# SCH_Fulcrum-Analog-FCU_2024-12-11.net
KiCad netlist of a schematic drawn in EasyEDA
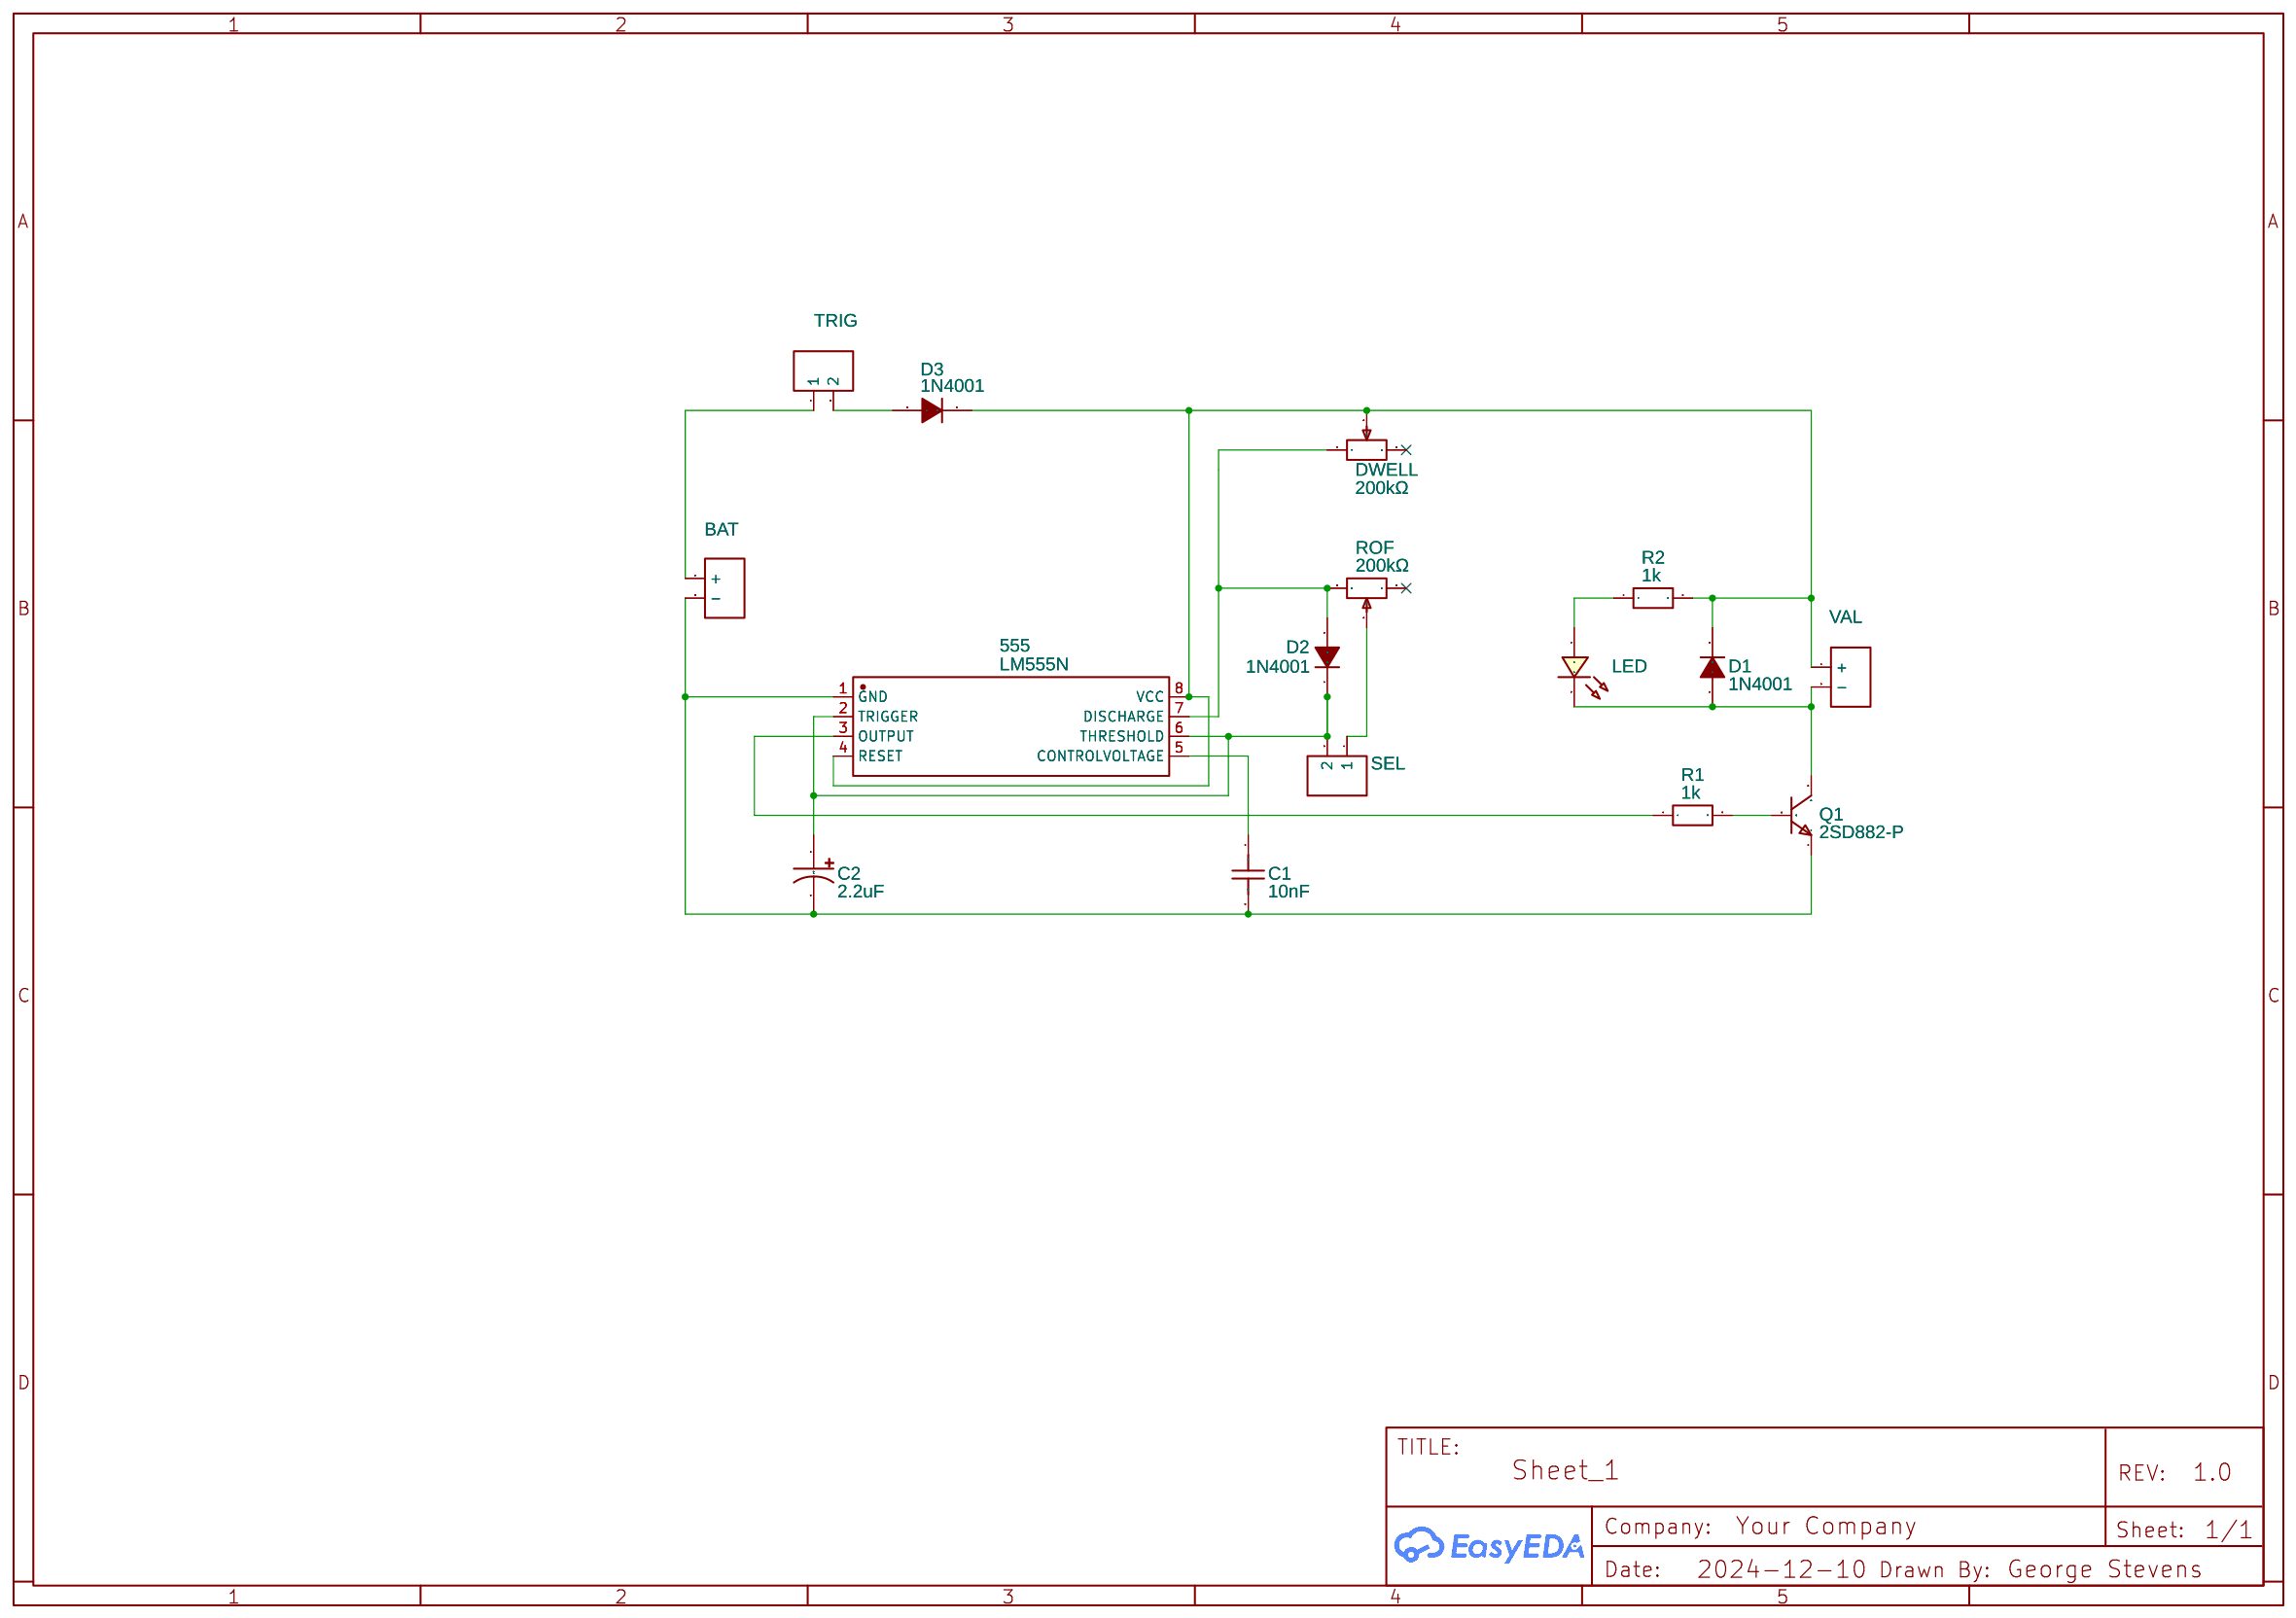
[diagram p0: schematic sheet]

(export (version "E")
  (design (tool "Eeschema 10.0.6"))
  (components
    (comp (ref "555")
      (value "LM555N")
      (fields (field (name "Manufacturer") "HGSEMI(华冠)"))
      (libsource (lib "") (part "LM555N"))
    )
    (comp (ref "BAT") (value "HDR-M-2.54_1x2") (libsource (lib "") (part "HDR-M-2.54_1x2")))
    (comp (ref "C1")
      (value "10nF")
      (fields (field (name "Manufacturer Part") "CL112J103J0501") (field (name "Manufacturer") "KYET(科雅)"))
      (libsource (lib "") (part "CL112J103J0501"))
    )
    (comp (ref "C2")
      (value "2.2uF")
      (fields
        (field (name "Manufacturer Part") "ECG1HM2R2D11OTBO")
        (field (name "Manufacturer") "Yunxing(云星)")
      )
      (libsource (lib "") (part "ECG1HM2R2D11OTBO"))
    )
    (comp (ref "D1")
      (value "1N4001")
      (fields (field (name "Manufacturer") "MDD(辰达半导体)"))
      (libsource (lib "") (part "1N4001_C2456"))
    )
    (comp (ref "D2")
      (value "1N4001")
      (fields (field (name "Manufacturer") "MDD(辰达半导体)"))
      (libsource (lib "") (part "1N4001_C2456_1"))
    )
    (comp (ref "D3")
      (value "1N4001")
      (fields (field (name "Manufacturer") "MDD(辰达半导体)"))
      (libsource (lib "") (part "1N4001_C2456_2"))
    )
    (comp (ref "DWELL")
      (value "200kΩ")
      (fields (field (name "Manufacturer Part") "RM063-204(200K)") (field (name "Manufacturer") "BOCHEN(博晨)"))
      (libsource (lib "") (part "RM063-204(200K)_1"))
    )
    (comp (ref "LED")
      (value "LED-TH-3mm_R")
      (fields
        (field (name "Manufacturer Part") "204-10SDRD/S530-A3-L")
        (field (name "Manufacturer") "EVERLIGHT(台湾亿光)")
      )
      (libsource (lib "") (part "LED-TH-3mm_R"))
    )
    (comp (ref "Q1")
      (value "2SD882-P")
      (fields (field (name "Manufacturer") "BLUE ROCKET(蓝箭)"))
      (libsource (lib "") (part "2SD882-P"))
    )
    (comp (ref "R1") (value "1k") (libsource (lib "") (part "R_AXIAL-0.4_EU")))
    (comp (ref "R2") (value "1k") (libsource (lib "") (part "R_AXIAL-0.4_EU")))
    (comp (ref "ROF")
      (value "200kΩ")
      (fields (field (name "Manufacturer Part") "RM063-204(200K)") (field (name "Manufacturer") "BOCHEN(博晨)"))
      (libsource (lib "") (part "RM063-204(200K)"))
    )
    (comp (ref "SEL") (value "HDR-M-2.54_1x2") (libsource (lib "") (part "HDR-M-2.54_1x2_3")))
    (comp (ref "TRIG") (value "HDR-M-2.54_1x2") (libsource (lib "") (part "HDR-M-2.54_1x2_2")))
    (comp (ref "VAL") (value "HDR-M-2.54_1x2") (libsource (lib "") (part "HDR-M-2.54_1x2_1")))
  )
  (nets
    (net (code "1") (name "Net-(555-CONTROLVOLTAGE)") (class "Default")
      (node (ref "555") (pin "5") (pinfunction "CONTROLVOLTAGE_5") (pintype "unspecified"))
      (node (ref "C1") (pin "1") (pinfunction "1_1") (pintype "unspecified"))
    )
    (net (code "2") (name "Net-(555-DISCHARGE)") (class "Default")
      (node (ref "555") (pin "7") (pinfunction "DISCHARGE_7") (pintype "unspecified"))
      (node (ref "D2") (pin "2") (pinfunction "A_2") (pintype "unspecified"))
      (node (ref "DWELL") (pin "1") (pinfunction "1_1") (pintype "input"))
      (node (ref "ROF") (pin "3") (pinfunction "3_3") (pintype "input"))
    )
    (net (code "3") (name "Net-(555-GND)") (class "Default")
      (node (ref "555") (pin "1") (pinfunction "GND_1") (pintype "unspecified"))
      (node (ref "BAT") (pin "2") (pinfunction "-_2") (pintype "unspecified"))
      (node (ref "C1") (pin "2") (pinfunction "2_2") (pintype "unspecified"))
      (node (ref "C2") (pin "2") (pinfunction "2_2") (pintype "unspecified"))
      (node (ref "Q1") (pin "1") (pinfunction "E_1") (pintype "unspecified"))
    )
    (net (code "4") (name "Net-(555-OUTPUT)") (class "Default")
      (node (ref "555") (pin "3") (pinfunction "OUTPUT_3") (pintype "unspecified"))
      (node (ref "R1") (pin "1") (pinfunction "1_1") (pintype "unspecified"))
    )
    (net (code "5") (name "Net-(555-RESET)") (class "Default")
      (node (ref "555") (pin "4") (pinfunction "RESET_4") (pintype "unspecified"))
      (node (ref "555") (pin "8") (pinfunction "VCC_8") (pintype "unspecified"))
      (node (ref "D1") (pin "1") (pinfunction "C_1") (pintype "unspecified"))
      (node (ref "D3") (pin "1") (pinfunction "C_1") (pintype "unspecified"))
      (node (ref "DWELL") (pin "2") (pinfunction "2_2") (pintype "input"))
      (node (ref "R2") (pin "2") (pinfunction "2_2") (pintype "unspecified"))
      (node (ref "VAL") (pin "1") (pinfunction "+_1") (pintype "unspecified"))
    )
    (net (code "6") (name "Net-(555-THRESHOLD)") (class "Default")
      (node (ref "555") (pin "2") (pinfunction "TRIGGER_2") (pintype "unspecified"))
      (node (ref "555") (pin "6") (pinfunction "THRESHOLD_6") (pintype "unspecified"))
      (node (ref "C2") (pin "1") (pinfunction "1_1") (pintype "unspecified"))
      (node (ref "D2") (pin "1") (pinfunction "C_1") (pintype "unspecified"))
      (node (ref "SEL") (pin "2") (pinfunction "2_2") (pintype "unspecified"))
    )
    (net (code "7") (name "Net-(BAT-+)") (class "Default")
      (node (ref "BAT") (pin "1") (pinfunction "+_1") (pintype "unspecified"))
      (node (ref "TRIG") (pin "1") (pinfunction "1_1") (pintype "unspecified"))
    )
    (net (code "8") (name "Net-(D1-A)") (class "Default")
      (node (ref "D1") (pin "2") (pinfunction "A_2") (pintype "unspecified"))
      (node (ref "LED") (pin "2") (pinfunction "2_2") (pintype "unspecified"))
      (node (ref "Q1") (pin "2") (pinfunction "C_2") (pintype "unspecified"))
      (node (ref "VAL") (pin "2") (pinfunction "-_2") (pintype "unspecified"))
    )
    (net (code "9") (name "Net-(D3-A)") (class "Default")
      (node (ref "D3") (pin "2") (pinfunction "A_2") (pintype "unspecified"))
      (node (ref "TRIG") (pin "2") (pinfunction "2_2") (pintype "unspecified"))
    )
    (net (code "10") (name "Net-(LED-Pad1)") (class "Default")
      (node (ref "LED") (pin "1") (pinfunction "1_1") (pintype "unspecified"))
      (node (ref "R2") (pin "1") (pinfunction "1_1") (pintype "unspecified"))
    )
    (net (code "11") (name "Net-(Q1-B)") (class "Default")
      (node (ref "Q1") (pin "3") (pinfunction "B_3") (pintype "unspecified"))
      (node (ref "R1") (pin "2") (pinfunction "2_2") (pintype "unspecified"))
    )
    (net (code "12") (name "Net-(ROF-Pad2)") (class "Default")
      (node (ref "ROF") (pin "2") (pinfunction "2_2") (pintype "input"))
      (node (ref "SEL") (pin "1") (pinfunction "1_1") (pintype "unspecified"))
    )
    (net (code "13") (name "unconnected-(DWELL-Pad3)") (class "Default")
      (node (ref "DWELL") (pin "3") (pinfunction "3_3") (pintype "input+no_connect"))
    )
    (net (code "14") (name "unconnected-(ROF-Pad1)") (class "Default")
      (node (ref "ROF") (pin "1") (pinfunction "1_1") (pintype "input+no_connect"))
    )
  )
)
